# SCH_Portoise2_0_2024-07-26.net
KiCad netlist of a schematic drawn in EasyEDA
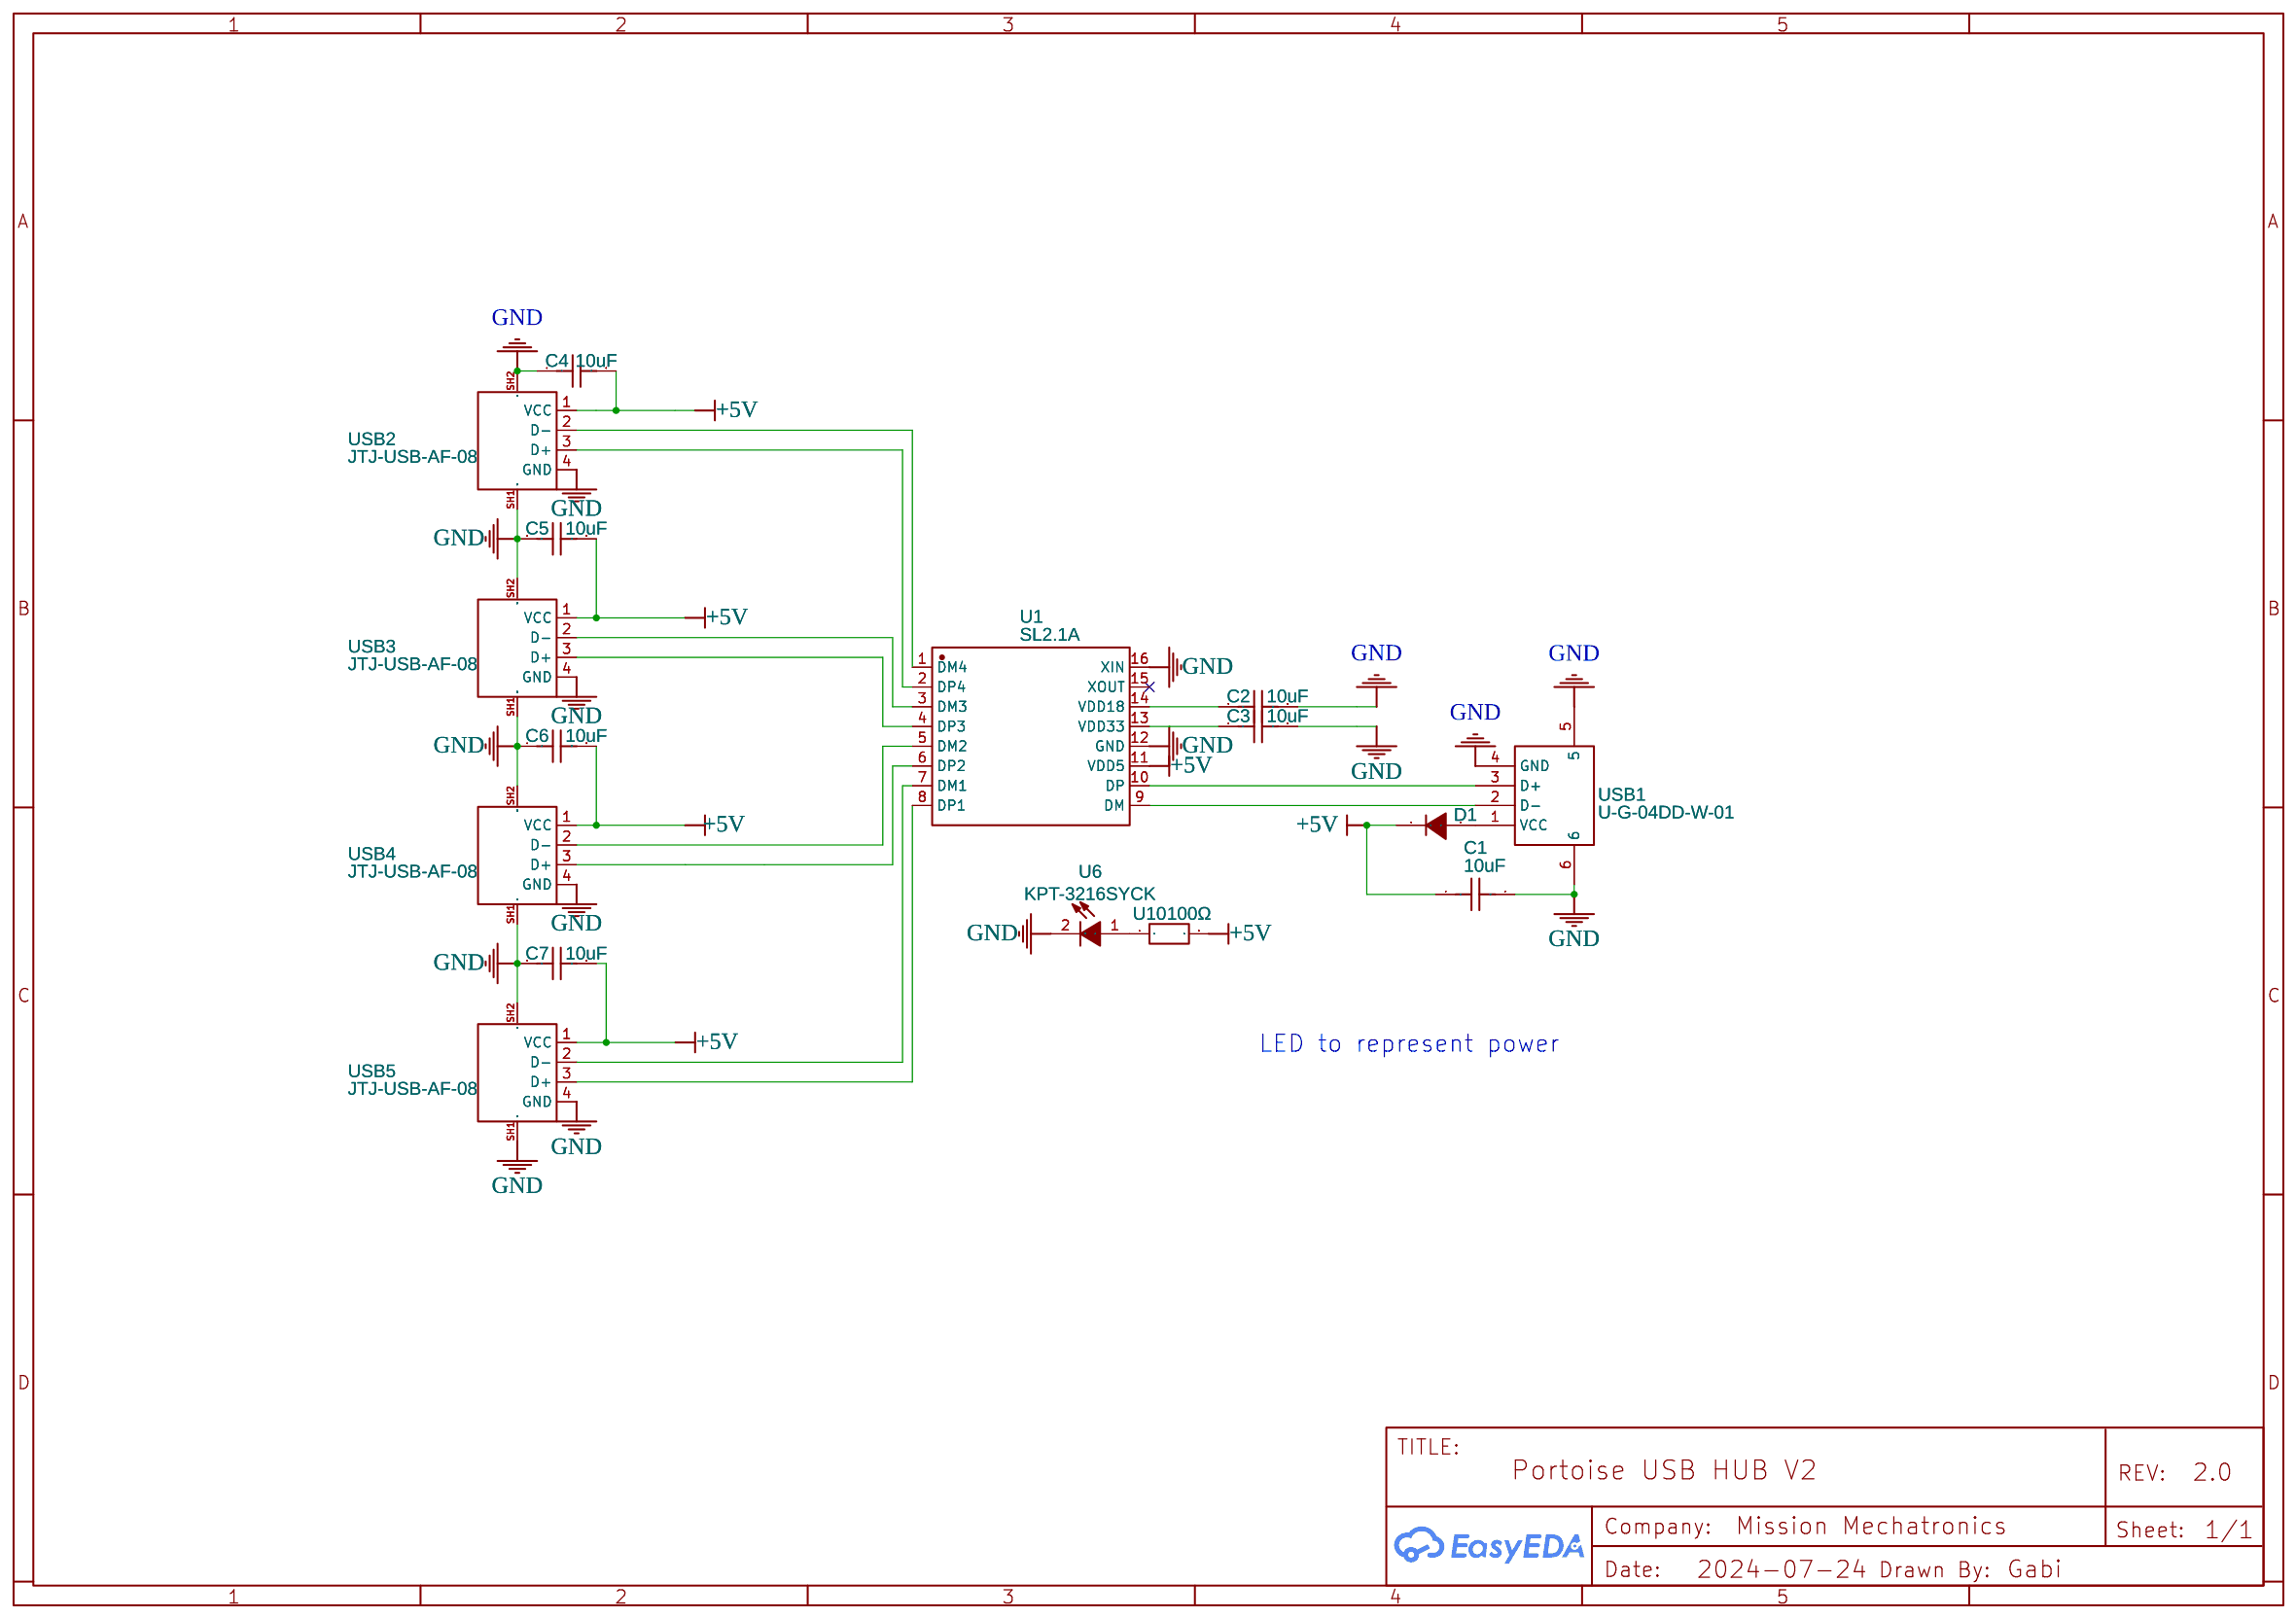
[diagram p0: schematic sheet]

(export (version "E")
  (design (tool "Eeschema 10.0.6"))
  (components
    (comp (ref "C1")
      (value "10uF")
      (fields
        (field (name "Manufacturer Part") "CL10A106KP8NNNC")
        (field (name "Manufacturer") "SAMSUNG(三星)")
      )
      (libsource (lib "") (part "CL10A106KP8NNNC"))
    )
    (comp (ref "C2")
      (value "10uF")
      (fields
        (field (name "Manufacturer Part") "CL10A106KP8NNNC")
        (field (name "Manufacturer") "SAMSUNG(三星)")
      )
      (libsource (lib "") (part "CL10A106KP8NNNC"))
    )
    (comp (ref "C3")
      (value "10uF")
      (fields
        (field (name "Manufacturer Part") "CL10A106KP8NNNC")
        (field (name "Manufacturer") "SAMSUNG(三星)")
      )
      (libsource (lib "") (part "CL10A106KP8NNNC"))
    )
    (comp (ref "C4")
      (value "10uF")
      (fields
        (field (name "Manufacturer Part") "CL10A106KP8NNNC")
        (field (name "Manufacturer") "SAMSUNG(三星)")
      )
      (libsource (lib "") (part "CL10A106KP8NNNC"))
    )
    (comp (ref "C5")
      (value "10uF")
      (fields
        (field (name "Manufacturer Part") "CL10A106KP8NNNC")
        (field (name "Manufacturer") "SAMSUNG(三星)")
      )
      (libsource (lib "") (part "CL10A106KP8NNNC"))
    )
    (comp (ref "C6")
      (value "10uF")
      (fields
        (field (name "Manufacturer Part") "CL10A106KP8NNNC")
        (field (name "Manufacturer") "SAMSUNG(三星)")
      )
      (libsource (lib "") (part "CL10A106KP8NNNC"))
    )
    (comp (ref "C7")
      (value "10uF")
      (fields
        (field (name "Manufacturer Part") "CL10A106KP8NNNC")
        (field (name "Manufacturer") "SAMSUNG(三星)")
      )
      (libsource (lib "") (part "CL10A106KP8NNNC"))
    )
    (comp (ref "D1")
      (value "NSR0320MW2T1G")
      (fields (field (name "Manufacturer") "onsemi(安森美)"))
      (libsource (lib "") (part "NSR0320MW2T1G"))
    )
    (comp (ref "U1")
      (value "SL2.1A")
      (fields (field (name "Manufacturer") "CoreChips(和芯润德)"))
      (libsource (lib "") (part "SL2.1A"))
    )
    (comp (ref "U6")
      (value "KPT-3216SYCK")
      (fields (field (name "Manufacturer") "Kingbright"))
      (libsource (lib "") (part "KPT-3216SYCK"))
    )
    (comp (ref "U10")
      (value "100Ω")
      (fields (field (name "Manufacturer Part") "OX101KE") (field (name "Manufacturer") "Ohmite"))
      (libsource (lib "") (part "OX101KE"))
    )
    (comp (ref "USB1")
      (value "U-G-04DD-W-01")
      (fields (field (name "Manufacturer Part") "U-G-O4DD-W-1") (field (name "Manufacturer") "韩国韩荣"))
      (libsource (lib "") (part "U-G-04DD-W-01"))
    )
    (comp (ref "USB2")
      (value "JTJ-USB-AF-08")
      (fields (field (name "Manufacturer Part") "902-131A1011D10100") (field (name "Manufacturer") "精拓金"))
      (libsource (lib "") (part "JTJ-USB-AF-08"))
    )
    (comp (ref "USB3")
      (value "JTJ-USB-AF-08")
      (fields (field (name "Manufacturer Part") "902-131A1011D10100") (field (name "Manufacturer") "精拓金"))
      (libsource (lib "") (part "JTJ-USB-AF-08"))
    )
    (comp (ref "USB4")
      (value "JTJ-USB-AF-08")
      (fields (field (name "Manufacturer Part") "902-131A1011D10100") (field (name "Manufacturer") "精拓金"))
      (libsource (lib "") (part "JTJ-USB-AF-08"))
    )
    (comp (ref "USB5")
      (value "JTJ-USB-AF-08")
      (fields (field (name "Manufacturer Part") "902-131A1011D10100") (field (name "Manufacturer") "精拓金"))
      (libsource (lib "") (part "JTJ-USB-AF-08"))
    )
  )
  (nets
    (net (code "1") (name "+5V") (class "Default")
      (node (ref "C1") (pin "1") (pinfunction "1_1") (pintype "unspecified"))
      (node (ref "C4") (pin "2") (pinfunction "2_2") (pintype "unspecified"))
      (node (ref "C5") (pin "2") (pinfunction "2_2") (pintype "unspecified"))
      (node (ref "C6") (pin "2") (pinfunction "2_2") (pintype "unspecified"))
      (node (ref "C7") (pin "2") (pinfunction "2_2") (pintype "unspecified"))
      (node (ref "D1") (pin "1") (pinfunction "C_1") (pintype "unspecified"))
      (node (ref "U1") (pin "11") (pinfunction "VDD5_11") (pintype "unspecified"))
      (node (ref "U10") (pin "2") (pinfunction "2_2") (pintype "unspecified"))
      (node (ref "USB2") (pin "1") (pinfunction "VCC_1") (pintype "input"))
      (node (ref "USB3") (pin "1") (pinfunction "VCC_1") (pintype "input"))
      (node (ref "USB4") (pin "1") (pinfunction "VCC_1") (pintype "input"))
      (node (ref "USB5") (pin "1") (pinfunction "VCC_1") (pintype "input"))
    )
    (net (code "2") (name "GND") (class "Default")
      (node (ref "C1") (pin "2") (pinfunction "2_2") (pintype "unspecified"))
      (node (ref "C2") (pin "2") (pinfunction "2_2") (pintype "unspecified"))
      (node (ref "C3") (pin "2") (pinfunction "2_2") (pintype "unspecified"))
      (node (ref "C4") (pin "1") (pinfunction "1_1") (pintype "unspecified"))
      (node (ref "C5") (pin "1") (pinfunction "1_1") (pintype "unspecified"))
      (node (ref "C6") (pin "1") (pinfunction "1_1") (pintype "unspecified"))
      (node (ref "C7") (pin "1") (pinfunction "1_1") (pintype "unspecified"))
      (node (ref "U1") (pin "12") (pinfunction "GND_12") (pintype "unspecified"))
      (node (ref "U1") (pin "16") (pinfunction "XIN_16") (pintype "unspecified"))
      (node (ref "U6") (pin "2") (pinfunction "C_2") (pintype "input"))
      (node (ref "USB1") (pin "4") (pinfunction "GND_4") (pintype "unspecified"))
      (node (ref "USB1") (pin "5") (pinfunction "5_5") (pintype "unspecified"))
      (node (ref "USB1") (pin "6") (pinfunction "6_6") (pintype "unspecified"))
      (node (ref "USB2") (pin "4") (pinfunction "GND_4") (pintype "input"))
      (node (ref "USB2") (pin "SH1") (pinfunction "SH1_SH1") (pintype "unspecified"))
      (node (ref "USB2") (pin "SH2") (pinfunction "SH2_SH2") (pintype "unspecified"))
      (node (ref "USB3") (pin "4") (pinfunction "GND_4") (pintype "input"))
      (node (ref "USB3") (pin "SH1") (pinfunction "SH1_SH1") (pintype "unspecified"))
      (node (ref "USB3") (pin "SH2") (pinfunction "SH2_SH2") (pintype "unspecified"))
      (node (ref "USB4") (pin "4") (pinfunction "GND_4") (pintype "input"))
      (node (ref "USB4") (pin "SH1") (pinfunction "SH1_SH1") (pintype "unspecified"))
      (node (ref "USB4") (pin "SH2") (pinfunction "SH2_SH2") (pintype "unspecified"))
      (node (ref "USB5") (pin "4") (pinfunction "GND_4") (pintype "input"))
      (node (ref "USB5") (pin "SH1") (pinfunction "SH1_SH1") (pintype "unspecified"))
      (node (ref "USB5") (pin "SH2") (pinfunction "SH2_SH2") (pintype "unspecified"))
    )
    (net (code "3") (name "Net-(D1-A)") (class "Default")
      (node (ref "D1") (pin "2") (pinfunction "A_2") (pintype "unspecified"))
      (node (ref "USB1") (pin "1") (pinfunction "VCC_1") (pintype "unspecified"))
    )
    (net (code "4") (name "Net-(U1-DM)") (class "Default")
      (node (ref "U1") (pin "9") (pinfunction "DM_9") (pintype "unspecified"))
      (node (ref "USB1") (pin "2") (pinfunction "D-_2") (pintype "unspecified"))
    )
    (net (code "5") (name "Net-(U1-DM1)") (class "Default")
      (node (ref "U1") (pin "7") (pinfunction "DM1_7") (pintype "unspecified"))
      (node (ref "USB5") (pin "2") (pinfunction "D-_2") (pintype "input"))
    )
    (net (code "6") (name "Net-(U1-DM2)") (class "Default")
      (node (ref "U1") (pin "5") (pinfunction "DM2_5") (pintype "unspecified"))
      (node (ref "USB4") (pin "2") (pinfunction "D-_2") (pintype "input"))
    )
    (net (code "7") (name "Net-(U1-DM3)") (class "Default")
      (node (ref "U1") (pin "3") (pinfunction "DM3_3") (pintype "unspecified"))
      (node (ref "USB3") (pin "2") (pinfunction "D-_2") (pintype "input"))
    )
    (net (code "8") (name "Net-(U1-DM4)") (class "Default")
      (node (ref "U1") (pin "1") (pinfunction "DM4_1") (pintype "unspecified"))
      (node (ref "USB2") (pin "2") (pinfunction "D-_2") (pintype "input"))
    )
    (net (code "9") (name "Net-(U1-DP)") (class "Default")
      (node (ref "U1") (pin "10") (pinfunction "DP_10") (pintype "unspecified"))
      (node (ref "USB1") (pin "3") (pinfunction "D+_3") (pintype "unspecified"))
    )
    (net (code "10") (name "Net-(U1-DP1)") (class "Default")
      (node (ref "U1") (pin "8") (pinfunction "DP1_8") (pintype "unspecified"))
      (node (ref "USB5") (pin "3") (pinfunction "D+_3") (pintype "input"))
    )
    (net (code "11") (name "Net-(U1-DP2)") (class "Default")
      (node (ref "U1") (pin "6") (pinfunction "DP2_6") (pintype "unspecified"))
      (node (ref "USB4") (pin "3") (pinfunction "D+_3") (pintype "input"))
    )
    (net (code "12") (name "Net-(U1-DP3)") (class "Default")
      (node (ref "U1") (pin "4") (pinfunction "DP3_4") (pintype "unspecified"))
      (node (ref "USB3") (pin "3") (pinfunction "D+_3") (pintype "input"))
    )
    (net (code "13") (name "Net-(U1-DP4)") (class "Default")
      (node (ref "U1") (pin "2") (pinfunction "DP4_2") (pintype "unspecified"))
      (node (ref "USB2") (pin "3") (pinfunction "D+_3") (pintype "input"))
    )
    (net (code "14") (name "Net-(U1-VDD18)") (class "Default")
      (node (ref "C2") (pin "1") (pinfunction "1_1") (pintype "unspecified"))
      (node (ref "U1") (pin "14") (pinfunction "VDD18_14") (pintype "unspecified"))
    )
    (net (code "15") (name "Net-(U1-VDD33)") (class "Default")
      (node (ref "C3") (pin "1") (pinfunction "1_1") (pintype "unspecified"))
      (node (ref "U1") (pin "13") (pinfunction "VDD33_13") (pintype "unspecified"))
    )
    (net (code "16") (name "Net-(U6-A)") (class "Default")
      (node (ref "U10") (pin "1") (pinfunction "1_1") (pintype "unspecified"))
      (node (ref "U6") (pin "1") (pinfunction "A_1") (pintype "input"))
    )
    (net (code "17") (name "unconnected-(U1-XOUT-Pad15)") (class "Default")
      (node (ref "U1") (pin "15") (pinfunction "XOUT_15") (pintype "unspecified+no_connect"))
    )
  )
)
